# Arduino_Micro_DRAM_Tester_2.net
KiCad netlist of a schematic drawn in EAGLE
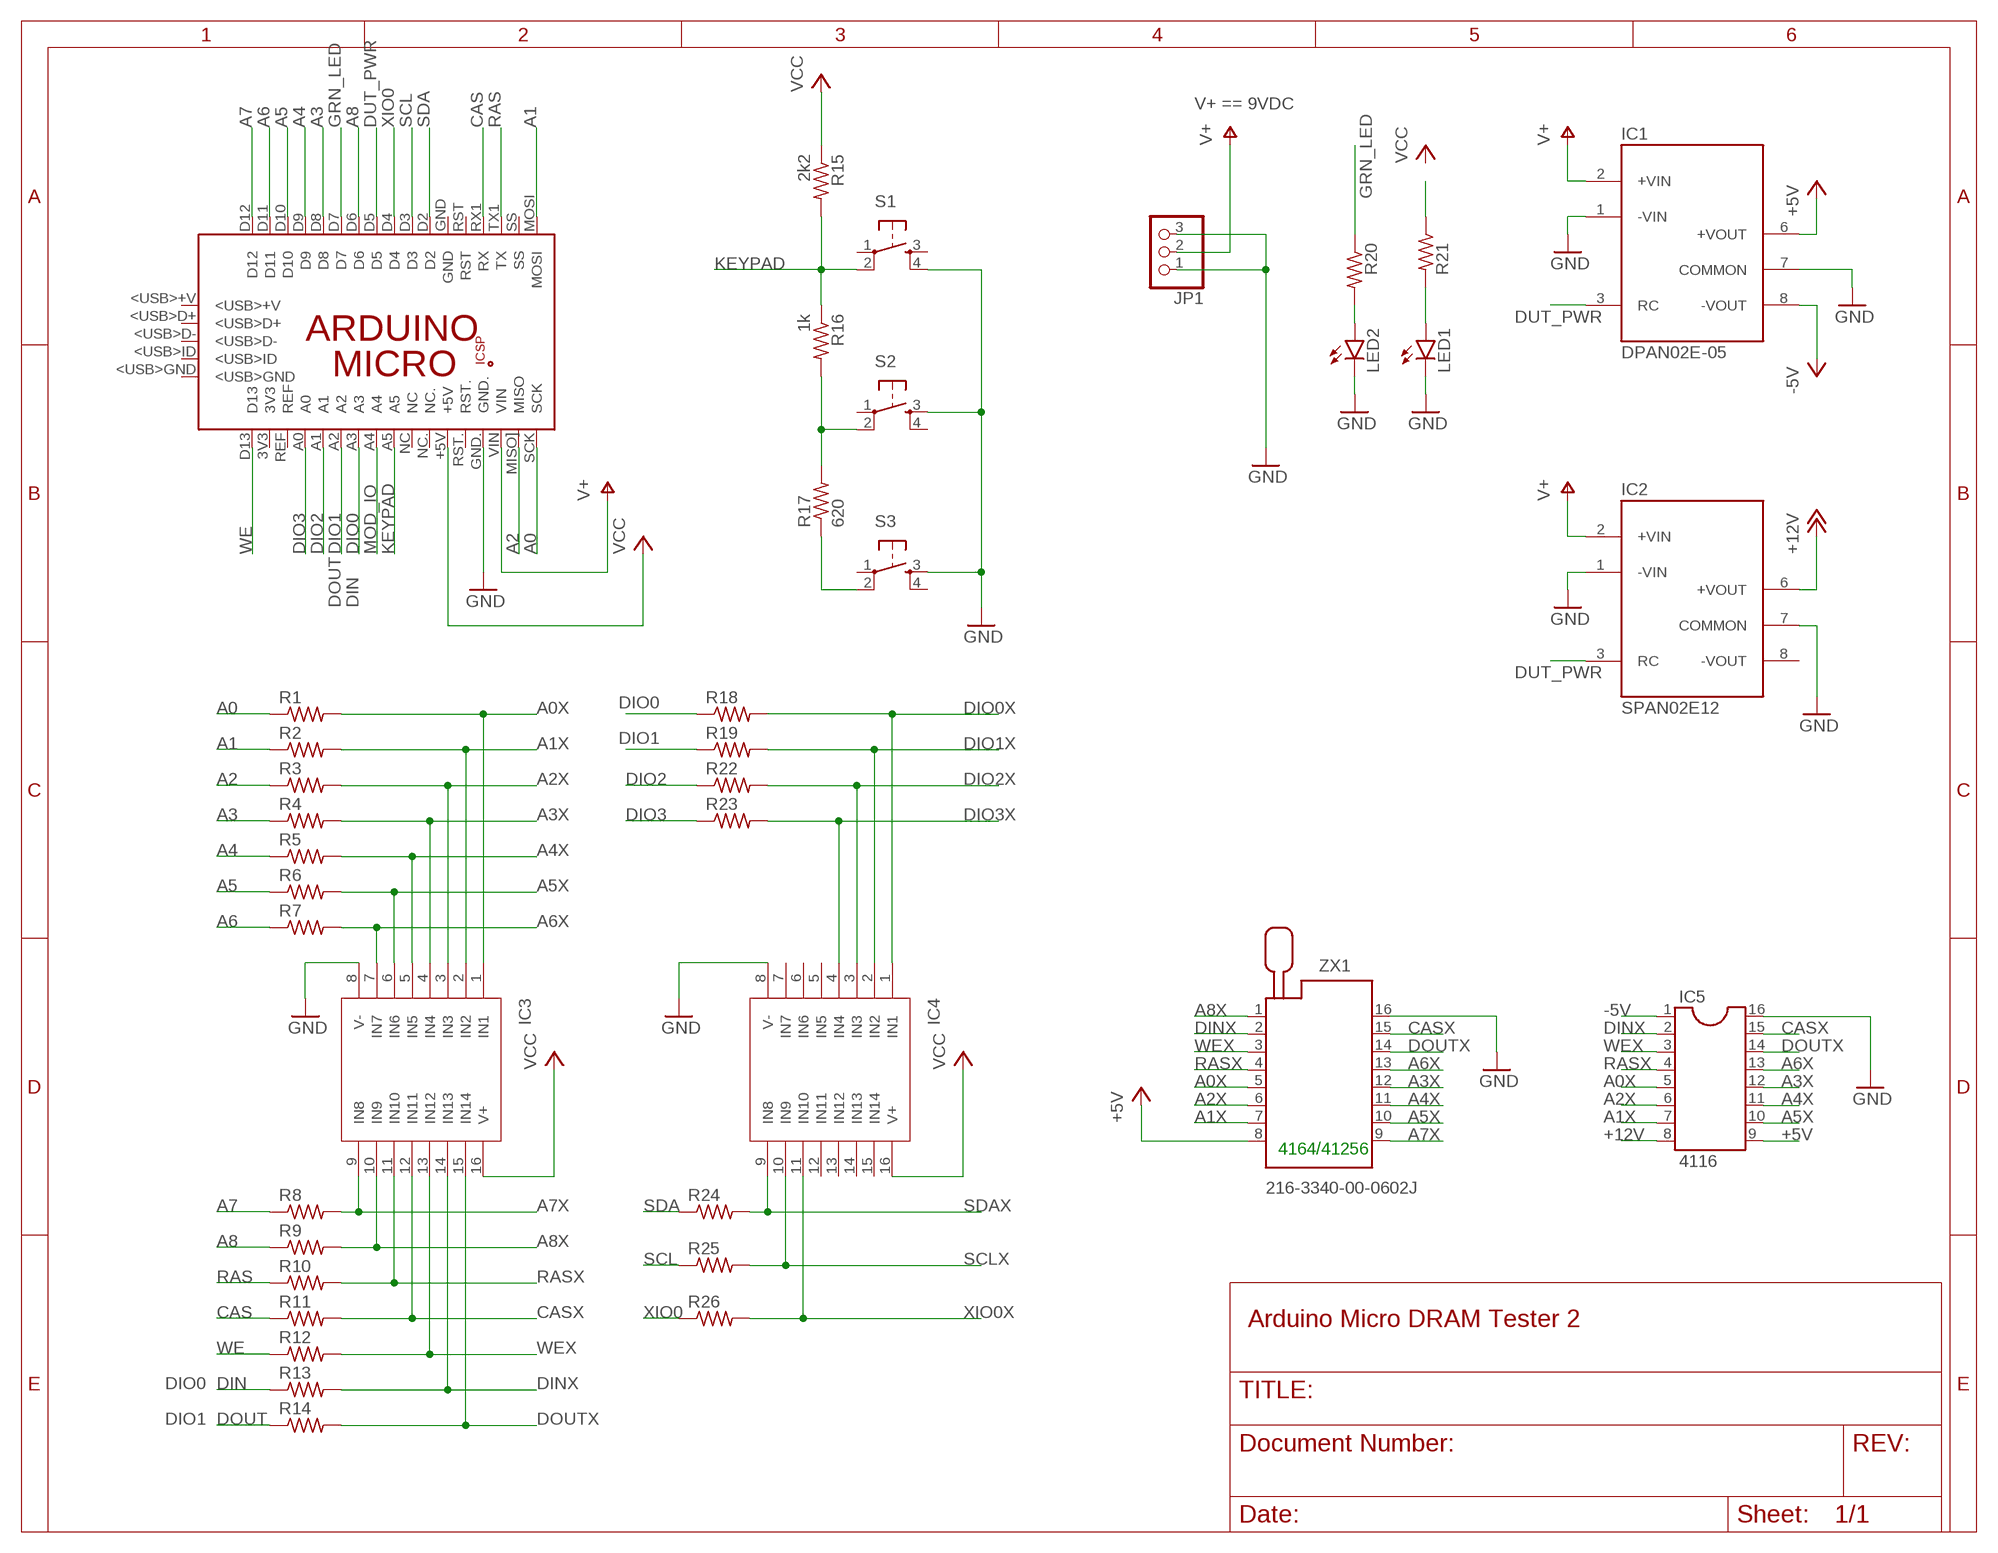
[diagram p0: schematic, sheet 1]

(export (version "E")
  (design (tool "Eeschema 10.0.6"))
  (components
    (comp (ref "IC1")
      (value "DPAN02E-05")
      (footprint "eagle-import:SIP7")
      (libsource (lib "eagle-import") (part "DPAN02"))
    )
    (comp (ref "IC2")
      (value "SPAN02E12")
      (footprint "eagle-import:SIP7")
      (libsource (lib "eagle-import") (part "DPAN02"))
    )
    (comp (ref "IC3")
      (value "SP720")
      (footprint "eagle-import:DIL16")
      (libsource (lib "eagle-import") (part "SP720"))
    )
    (comp (ref "IC4")
      (value "SP720")
      (footprint "eagle-import:DIL16")
      (libsource (lib "eagle-import") (part "SP720"))
    )
    (comp (ref "IC5")
      (value "4116")
      (footprint "eagle-import:SOCKET-16")
      (libsource (lib "eagle-import") (part "DIL16S"))
    )
    (comp (ref "JP1")
      (value "PINHD-1X3/90")
      (footprint "eagle-import:1X03_90")
      (libsource (lib "eagle-import") (part "PINHD-1X3/90"))
    )
    (comp (ref "LED1")
      (value "LED5MM")
      (footprint "eagle-import:LED5MM")
      (libsource (lib "eagle-import") (part "LED5MM"))
    )
    (comp (ref "LED2")
      (value "LED5MM")
      (footprint "eagle-import:LED5MM")
      (libsource (lib "eagle-import") (part "LED5MM"))
    )
    (comp (ref "PCB1")
      (value "ARDUINO_MICRO")
      (footprint "eagle-import:ARDUINO_MICRO")
      (libsource (lib "eagle-import") (part "ARDUINO_MICRO"))
    )
    (comp (ref "R1")
      (value "R-US_V235/17")
      (footprint "eagle-import:V235_17")
      (libsource (lib "eagle-import") (part "R-US_V235/17"))
    )
    (comp (ref "R2")
      (value "R-US_V235/17")
      (footprint "eagle-import:V235_17")
      (libsource (lib "eagle-import") (part "R-US_V235/17"))
    )
    (comp (ref "R3")
      (value "R-US_V235/17")
      (footprint "eagle-import:V235_17")
      (libsource (lib "eagle-import") (part "R-US_V235/17"))
    )
    (comp (ref "R4")
      (value "R-US_V235/17")
      (footprint "eagle-import:V235_17")
      (libsource (lib "eagle-import") (part "R-US_V235/17"))
    )
    (comp (ref "R5")
      (value "R-US_V235/17")
      (footprint "eagle-import:V235_17")
      (libsource (lib "eagle-import") (part "R-US_V235/17"))
    )
    (comp (ref "R6")
      (value "R-US_V235/17")
      (footprint "eagle-import:V235_17")
      (libsource (lib "eagle-import") (part "R-US_V235/17"))
    )
    (comp (ref "R7")
      (value "R-US_V235/17")
      (footprint "eagle-import:V235_17")
      (libsource (lib "eagle-import") (part "R-US_V235/17"))
    )
    (comp (ref "R8")
      (value "R-US_V235/17")
      (footprint "eagle-import:V235_17")
      (libsource (lib "eagle-import") (part "R-US_V235/17"))
    )
    (comp (ref "R9")
      (value "R-US_V235/17")
      (footprint "eagle-import:V235_17")
      (libsource (lib "eagle-import") (part "R-US_V235/17"))
    )
    (comp (ref "R10")
      (value "R-US_V235/17")
      (footprint "eagle-import:V235_17")
      (libsource (lib "eagle-import") (part "R-US_V235/17"))
    )
    (comp (ref "R11")
      (value "R-US_V235/17")
      (footprint "eagle-import:V235_17")
      (libsource (lib "eagle-import") (part "R-US_V235/17"))
    )
    (comp (ref "R12")
      (value "R-US_V235/17")
      (footprint "eagle-import:V235_17")
      (libsource (lib "eagle-import") (part "R-US_V235/17"))
    )
    (comp (ref "R13")
      (value "R-US_V235/17")
      (footprint "eagle-import:V235_17")
      (libsource (lib "eagle-import") (part "R-US_V235/17"))
    )
    (comp (ref "R14")
      (value "R-US_V235/17")
      (footprint "eagle-import:V235_17")
      (libsource (lib "eagle-import") (part "R-US_V235/17"))
    )
    (comp (ref "R15")
      (value "2k2")
      (footprint "eagle-import:V235_17")
      (libsource (lib "eagle-import") (part "R-US_V235/17"))
    )
    (comp (ref "R16")
      (value "1k")
      (footprint "eagle-import:V235_17")
      (libsource (lib "eagle-import") (part "R-US_V235/17"))
    )
    (comp (ref "R17")
      (value "620")
      (footprint "eagle-import:V235_17")
      (libsource (lib "eagle-import") (part "R-US_V235/17"))
    )
    (comp (ref "R18")
      (value "R-US_V235/17")
      (footprint "eagle-import:V235_17")
      (libsource (lib "eagle-import") (part "R-US_V235/17"))
    )
    (comp (ref "R19")
      (value "R-US_V235/17")
      (footprint "eagle-import:V235_17")
      (libsource (lib "eagle-import") (part "R-US_V235/17"))
    )
    (comp (ref "R20")
      (value "R-US_0309/10")
      (footprint "eagle-import:0309_10")
      (libsource (lib "eagle-import") (part "resistor_348_R-US_0309/10"))
    )
    (comp (ref "R21")
      (value "R-US_0309/10")
      (footprint "eagle-import:0309_10")
      (libsource (lib "eagle-import") (part "resistor_348_R-US_0309/10"))
    )
    (comp (ref "R22")
      (value "R-US_V235/17")
      (footprint "eagle-import:V235_17")
      (libsource (lib "eagle-import") (part "R-US_V235/17"))
    )
    (comp (ref "R23")
      (value "R-US_V235/17")
      (footprint "eagle-import:V235_17")
      (libsource (lib "eagle-import") (part "R-US_V235/17"))
    )
    (comp (ref "R24")
      (value "R-US_V235/17")
      (footprint "eagle-import:V235_17")
      (libsource (lib "eagle-import") (part "R-US_V235/17"))
    )
    (comp (ref "R25")
      (value "R-US_V235/17")
      (footprint "eagle-import:V235_17")
      (libsource (lib "eagle-import") (part "R-US_V235/17"))
    )
    (comp (ref "R26")
      (value "R-US_V235/17")
      (footprint "eagle-import:V235_17")
      (libsource (lib "eagle-import") (part "R-US_V235/17"))
    )
    (comp (ref "S1")
      (value "TAC_SWITCHPTH")
      (footprint "eagle-import:TACTILE-PTH")
      (libsource (lib "eagle-import") (part "TAC_SWITCHPTH"))
    )
    (comp (ref "S2")
      (value "TAC_SWITCHPTH")
      (footprint "eagle-import:TACTILE-PTH")
      (libsource (lib "eagle-import") (part "TAC_SWITCHPTH"))
    )
    (comp (ref "S3")
      (value "TAC_SWITCHPTH")
      (footprint "eagle-import:TACTILE-PTH")
      (libsource (lib "eagle-import") (part "TAC_SWITCHPTH"))
    )
    (comp (ref "ZX1")
      (value "216-3340-00-0602J")
      (footprint "eagle-import:216-3340-00-0602J")
      (libsource (lib "eagle-import") (part "216-3340-00-0602J"))
    )
  )
  (nets
    (net (code "1") (name "+5V") (class "Default")
      (node (ref "IC1") (pin "6") (pinfunction "+VOUT_6") (pintype "passive"))
      (node (ref "IC5") (pin "9") (pinfunction "9_9") (pintype "passive"))
      (node (ref "ZX1") (pin "8") (pinfunction "8_8") (pintype "passive"))
    )
    (net (code "2") (name "+12V") (class "Default")
      (node (ref "IC2") (pin "6") (pinfunction "+VOUT_6") (pintype "passive"))
      (node (ref "IC5") (pin "8") (pinfunction "8_8") (pintype "passive"))
    )
    (net (code "3") (name "-5V") (class "Default")
      (node (ref "IC1") (pin "8") (pinfunction "-VOUT_8") (pintype "passive"))
      (node (ref "IC5") (pin "1") (pinfunction "1_1") (pintype "passive"))
    )
    (net (code "4") (name "/A0") (class "Default")
      (node (ref "PCB1") (pin "SCK") (pinfunction "SCK_SCK") (pintype "bidirectional"))
      (node (ref "R1") (pin "1") (pinfunction "1_1") (pintype "passive"))
    )
    (net (code "5") (name "/A0X") (class "Default")
      (node (ref "IC3") (pin "1") (pinfunction "IN1_1") (pintype "input"))
      (node (ref "IC5") (pin "5") (pinfunction "5_5") (pintype "passive"))
      (node (ref "R1") (pin "2") (pinfunction "2_2") (pintype "passive"))
      (node (ref "ZX1") (pin "5") (pinfunction "5_5") (pintype "passive"))
    )
    (net (code "6") (name "/A1") (class "Default")
      (node (ref "PCB1") (pin "MOSI") (pinfunction "MOSI_MOSI") (pintype "bidirectional"))
      (node (ref "R2") (pin "1") (pinfunction "1_1") (pintype "passive"))
    )
    (net (code "7") (name "/A1X") (class "Default")
      (node (ref "IC3") (pin "2") (pinfunction "IN2_2") (pintype "input"))
      (node (ref "IC5") (pin "7") (pinfunction "7_7") (pintype "passive"))
      (node (ref "R2") (pin "2") (pinfunction "2_2") (pintype "passive"))
      (node (ref "ZX1") (pin "7") (pinfunction "7_7") (pintype "passive"))
    )
    (net (code "8") (name "/A2") (class "Default")
      (node (ref "PCB1") (pin "MISO]") (pinfunction "MISO_MISO]") (pintype "bidirectional"))
      (node (ref "R3") (pin "1") (pinfunction "1_1") (pintype "passive"))
    )
    (net (code "9") (name "/A2X") (class "Default")
      (node (ref "IC3") (pin "3") (pinfunction "IN3_3") (pintype "input"))
      (node (ref "IC5") (pin "6") (pinfunction "6_6") (pintype "passive"))
      (node (ref "R3") (pin "2") (pinfunction "2_2") (pintype "passive"))
      (node (ref "ZX1") (pin "6") (pinfunction "6_6") (pintype "passive"))
    )
    (net (code "10") (name "/A3") (class "Default")
      (node (ref "PCB1") (pin "D8") (pinfunction "D8_D8") (pintype "bidirectional"))
      (node (ref "R4") (pin "1") (pinfunction "1_1") (pintype "passive"))
    )
    (net (code "11") (name "/A3X") (class "Default")
      (node (ref "IC3") (pin "4") (pinfunction "IN4_4") (pintype "input"))
      (node (ref "IC5") (pin "12") (pinfunction "12_12") (pintype "passive"))
      (node (ref "R4") (pin "2") (pinfunction "2_2") (pintype "passive"))
      (node (ref "ZX1") (pin "12") (pinfunction "12_12") (pintype "passive"))
    )
    (net (code "12") (name "/A4") (class "Default")
      (node (ref "PCB1") (pin "D9") (pinfunction "D9_D9") (pintype "bidirectional"))
      (node (ref "R5") (pin "1") (pinfunction "1_1") (pintype "passive"))
    )
    (net (code "13") (name "/A4X") (class "Default")
      (node (ref "IC3") (pin "5") (pinfunction "IN5_5") (pintype "input"))
      (node (ref "IC5") (pin "11") (pinfunction "11_11") (pintype "passive"))
      (node (ref "R5") (pin "2") (pinfunction "2_2") (pintype "passive"))
      (node (ref "ZX1") (pin "11") (pinfunction "11_11") (pintype "passive"))
    )
    (net (code "14") (name "/A5") (class "Default")
      (node (ref "PCB1") (pin "D10") (pinfunction "D10_D10") (pintype "bidirectional"))
      (node (ref "R6") (pin "1") (pinfunction "1_1") (pintype "passive"))
    )
    (net (code "15") (name "/A5X") (class "Default")
      (node (ref "IC3") (pin "6") (pinfunction "IN6_6") (pintype "input"))
      (node (ref "IC5") (pin "10") (pinfunction "10_10") (pintype "passive"))
      (node (ref "R6") (pin "2") (pinfunction "2_2") (pintype "passive"))
      (node (ref "ZX1") (pin "10") (pinfunction "10_10") (pintype "passive"))
    )
    (net (code "16") (name "/A6") (class "Default")
      (node (ref "PCB1") (pin "D11") (pinfunction "D11_D11") (pintype "bidirectional"))
      (node (ref "R7") (pin "1") (pinfunction "1_1") (pintype "passive"))
    )
    (net (code "17") (name "/A6X") (class "Default")
      (node (ref "IC3") (pin "7") (pinfunction "IN7_7") (pintype "input"))
      (node (ref "IC5") (pin "13") (pinfunction "13_13") (pintype "passive"))
      (node (ref "R7") (pin "2") (pinfunction "2_2") (pintype "passive"))
      (node (ref "ZX1") (pin "13") (pinfunction "13_13") (pintype "passive"))
    )
    (net (code "18") (name "/A7") (class "Default")
      (node (ref "PCB1") (pin "D12") (pinfunction "D12_D12") (pintype "bidirectional"))
      (node (ref "R8") (pin "1") (pinfunction "1_1") (pintype "passive"))
    )
    (net (code "19") (name "/A7X") (class "Default")
      (node (ref "IC3") (pin "9") (pinfunction "IN8_9") (pintype "input"))
      (node (ref "R8") (pin "2") (pinfunction "2_2") (pintype "passive"))
      (node (ref "ZX1") (pin "9") (pinfunction "9_9") (pintype "passive"))
    )
    (net (code "20") (name "/A8") (class "Default")
      (node (ref "PCB1") (pin "D6") (pinfunction "D6_D6") (pintype "bidirectional"))
      (node (ref "R9") (pin "1") (pinfunction "1_1") (pintype "passive"))
    )
    (net (code "21") (name "/A8X") (class "Default")
      (node (ref "IC3") (pin "10") (pinfunction "IN9_10") (pintype "input"))
      (node (ref "R9") (pin "2") (pinfunction "2_2") (pintype "passive"))
      (node (ref "ZX1") (pin "1") (pinfunction "1_1") (pintype "passive"))
    )
    (net (code "22") (name "/CAS") (class "Default")
      (node (ref "PCB1") (pin "RX1") (pinfunction "RX_RX1") (pintype "bidirectional"))
      (node (ref "R11") (pin "1") (pinfunction "1_1") (pintype "passive"))
    )
    (net (code "23") (name "/CASX") (class "Default")
      (node (ref "IC3") (pin "12") (pinfunction "IN11_12") (pintype "input"))
      (node (ref "IC5") (pin "15") (pinfunction "15_15") (pintype "passive"))
      (node (ref "R11") (pin "2") (pinfunction "2_2") (pintype "passive"))
      (node (ref "ZX1") (pin "15") (pinfunction "15_15") (pintype "passive"))
    )
    (net (code "24") (name "/DIN") (class "Default")
      (node (ref "PCB1") (pin "A3") (pinfunction "A3_A3") (pintype "bidirectional"))
      (node (ref "R13") (pin "1") (pinfunction "1_1") (pintype "passive"))
    )
    (net (code "25") (name "/DINX") (class "Default")
      (node (ref "IC3") (pin "14") (pinfunction "IN13_14") (pintype "input"))
      (node (ref "IC5") (pin "2") (pinfunction "2_2") (pintype "passive"))
      (node (ref "R13") (pin "2") (pinfunction "2_2") (pintype "passive"))
      (node (ref "ZX1") (pin "2") (pinfunction "2_2") (pintype "passive"))
    )
    (net (code "26") (name "/DIO0X") (class "Default")
      (node (ref "IC4") (pin "1") (pinfunction "IN1_1") (pintype "input"))
      (node (ref "R18") (pin "2") (pinfunction "2_2") (pintype "passive"))
    )
    (net (code "27") (name "/DIO1X") (class "Default")
      (node (ref "IC4") (pin "2") (pinfunction "IN2_2") (pintype "input"))
      (node (ref "R19") (pin "2") (pinfunction "2_2") (pintype "passive"))
    )
    (net (code "28") (name "/DIO2") (class "Default")
      (node (ref "PCB1") (pin "A1") (pinfunction "A1_A1") (pintype "bidirectional"))
      (node (ref "R22") (pin "1") (pinfunction "1_1") (pintype "passive"))
    )
    (net (code "29") (name "/DIO2X") (class "Default")
      (node (ref "IC4") (pin "3") (pinfunction "IN3_3") (pintype "input"))
      (node (ref "R22") (pin "2") (pinfunction "2_2") (pintype "passive"))
    )
    (net (code "30") (name "/DIO3") (class "Default")
      (node (ref "PCB1") (pin "A0") (pinfunction "A0_A0") (pintype "bidirectional"))
      (node (ref "R23") (pin "1") (pinfunction "1_1") (pintype "passive"))
    )
    (net (code "31") (name "/DIO3X") (class "Default")
      (node (ref "IC4") (pin "4") (pinfunction "IN4_4") (pintype "input"))
      (node (ref "R23") (pin "2") (pinfunction "2_2") (pintype "passive"))
    )
    (net (code "32") (name "/DOUT") (class "Default")
      (node (ref "PCB1") (pin "A2") (pinfunction "A2_A2") (pintype "bidirectional"))
      (node (ref "R14") (pin "1") (pinfunction "1_1") (pintype "passive"))
    )
    (net (code "33") (name "/DOUTX") (class "Default")
      (node (ref "IC3") (pin "15") (pinfunction "IN14_15") (pintype "input"))
      (node (ref "IC5") (pin "14") (pinfunction "14_14") (pintype "passive"))
      (node (ref "R14") (pin "2") (pinfunction "2_2") (pintype "passive"))
      (node (ref "ZX1") (pin "14") (pinfunction "14_14") (pintype "passive"))
    )
    (net (code "34") (name "/DUT_PWR") (class "Default")
      (node (ref "IC1") (pin "3") (pinfunction "RC_3") (pintype "input"))
      (node (ref "IC2") (pin "3") (pinfunction "RC_3") (pintype "input"))
      (node (ref "PCB1") (pin "D5") (pinfunction "D5_D5") (pintype "bidirectional"))
    )
    (net (code "35") (name "/GRN_LED") (class "Default")
      (node (ref "PCB1") (pin "D7") (pinfunction "D7_D7") (pintype "bidirectional"))
      (node (ref "R20") (pin "1") (pinfunction "1_1") (pintype "passive"))
    )
    (net (code "36") (name "/KEYPAD") (class "Default")
      (node (ref "PCB1") (pin "A5") (pinfunction "A5_A5") (pintype "bidirectional"))
      (node (ref "R15") (pin "2") (pinfunction "2_2") (pintype "passive"))
      (node (ref "R16") (pin "1") (pinfunction "1_1") (pintype "passive"))
      (node (ref "S1") (pin "2") (pinfunction "2_2") (pintype "passive"))
    )
    (net (code "37") (name "/MOD_IO") (class "Default")
      (node (ref "PCB1") (pin "A4") (pinfunction "A4_A4") (pintype "bidirectional"))
    )
    (net (code "38") (name "/RAS") (class "Default")
      (node (ref "PCB1") (pin "TX1") (pinfunction "TX_TX1") (pintype "bidirectional"))
      (node (ref "R10") (pin "1") (pinfunction "1_1") (pintype "passive"))
    )
    (net (code "39") (name "/RASX") (class "Default")
      (node (ref "IC3") (pin "11") (pinfunction "IN10_11") (pintype "input"))
      (node (ref "IC5") (pin "4") (pinfunction "4_4") (pintype "passive"))
      (node (ref "R10") (pin "2") (pinfunction "2_2") (pintype "passive"))
      (node (ref "ZX1") (pin "4") (pinfunction "4_4") (pintype "passive"))
    )
    (net (code "40") (name "/SCL") (class "Default")
      (node (ref "PCB1") (pin "D3") (pinfunction "D3_D3") (pintype "bidirectional"))
      (node (ref "R25") (pin "1") (pinfunction "1_1") (pintype "passive"))
    )
    (net (code "41") (name "/SCLX") (class "Default")
      (node (ref "IC4") (pin "10") (pinfunction "IN9_10") (pintype "input"))
      (node (ref "R25") (pin "2") (pinfunction "2_2") (pintype "passive"))
    )
    (net (code "42") (name "/SDA") (class "Default")
      (node (ref "PCB1") (pin "D2") (pinfunction "D2_D2") (pintype "bidirectional"))
      (node (ref "R24") (pin "1") (pinfunction "1_1") (pintype "passive"))
    )
    (net (code "43") (name "/SDAX") (class "Default")
      (node (ref "IC4") (pin "9") (pinfunction "IN8_9") (pintype "input"))
      (node (ref "R24") (pin "2") (pinfunction "2_2") (pintype "passive"))
    )
    (net (code "44") (name "/WE") (class "Default")
      (node (ref "PCB1") (pin "D13") (pinfunction "D13_D13") (pintype "bidirectional"))
      (node (ref "R12") (pin "1") (pinfunction "1_1") (pintype "passive"))
    )
    (net (code "45") (name "/WEX") (class "Default")
      (node (ref "IC3") (pin "13") (pinfunction "IN12_13") (pintype "input"))
      (node (ref "IC5") (pin "3") (pinfunction "3_3") (pintype "passive"))
      (node (ref "R12") (pin "2") (pinfunction "2_2") (pintype "passive"))
      (node (ref "ZX1") (pin "3") (pinfunction "3_3") (pintype "passive"))
    )
    (net (code "46") (name "/XIO0") (class "Default")
      (node (ref "PCB1") (pin "D4") (pinfunction "D4_D4") (pintype "bidirectional"))
      (node (ref "R26") (pin "1") (pinfunction "1_1") (pintype "passive"))
    )
    (net (code "47") (name "/XIO0X") (class "Default")
      (node (ref "IC4") (pin "11") (pinfunction "IN10_11") (pintype "input"))
      (node (ref "R26") (pin "2") (pinfunction "2_2") (pintype "passive"))
    )
    (net (code "48") (name "GND") (class "Default")
      (node (ref "IC1") (pin "1") (pinfunction "-VIN_1") (pintype "input"))
      (node (ref "IC1") (pin "7") (pinfunction "COMMON_7") (pintype "passive"))
      (node (ref "IC2") (pin "1") (pinfunction "-VIN_1") (pintype "input"))
      (node (ref "IC2") (pin "7") (pinfunction "COMMON_7") (pintype "passive"))
      (node (ref "IC3") (pin "8") (pinfunction "V-_8") (pintype "input"))
      (node (ref "IC4") (pin "8") (pinfunction "V-_8") (pintype "input"))
      (node (ref "IC5") (pin "16") (pinfunction "16_16") (pintype "passive"))
      (node (ref "JP1") (pin "1") (pinfunction "1_1") (pintype "passive"))
      (node (ref "JP1") (pin "3") (pinfunction "3_3") (pintype "passive"))
      (node (ref "LED1") (pin "K") (pinfunction "C_K") (pintype "passive"))
      (node (ref "LED2") (pin "K") (pinfunction "C_K") (pintype "passive"))
      (node (ref "PCB1") (pin "GND.") (pinfunction "GND._GND.") (pintype "bidirectional"))
      (node (ref "S1") (pin "4") (pinfunction "4_4") (pintype "passive"))
      (node (ref "S2") (pin "3") (pinfunction "3_3") (pintype "passive"))
      (node (ref "S3") (pin "3") (pinfunction "3_3") (pintype "passive"))
      (node (ref "ZX1") (pin "16") (pinfunction "16_16") (pintype "passive"))
    )
    (net (code "49") (name "Net-(LED1-PadA)") (class "Default")
      (node (ref "LED1") (pin "A") (pinfunction "A_A") (pintype "passive"))
      (node (ref "R21") (pin "2") (pinfunction "2_2") (pintype "passive"))
    )
    (net (code "50") (name "Net-(LED2-PadA)") (class "Default")
      (node (ref "LED2") (pin "A") (pinfunction "A_A") (pintype "passive"))
      (node (ref "R20") (pin "2") (pinfunction "2_2") (pintype "passive"))
    )
    (net (code "51") (name "Net-(R16-Pad2)") (class "Default")
      (node (ref "R16") (pin "2") (pinfunction "2_2") (pintype "passive"))
      (node (ref "R17") (pin "2") (pinfunction "2_2") (pintype "passive"))
      (node (ref "S2") (pin "2") (pinfunction "2_2") (pintype "passive"))
    )
    (net (code "52") (name "Net-(R17-Pad1)") (class "Default")
      (node (ref "R17") (pin "1") (pinfunction "1_1") (pintype "passive"))
      (node (ref "S3") (pin "2") (pinfunction "2_2") (pintype "passive"))
    )
    (net (code "53") (name "V+") (class "Default")
      (node (ref "IC1") (pin "2") (pinfunction "+VIN_2") (pintype "input"))
      (node (ref "IC2") (pin "2") (pinfunction "+VIN_2") (pintype "input"))
      (node (ref "JP1") (pin "2") (pinfunction "2_2") (pintype "passive"))
      (node (ref "PCB1") (pin "VIN") (pinfunction "VIN_VIN") (pintype "bidirectional"))
    )
    (net (code "54") (name "VCC") (class "Default")
      (node (ref "IC3") (pin "16") (pinfunction "V+_16") (pintype "input"))
      (node (ref "IC4") (pin "16") (pinfunction "V+_16") (pintype "input"))
      (node (ref "PCB1") (pin "+5V") (pinfunction "+5V_+5V") (pintype "bidirectional"))
      (node (ref "R15") (pin "1") (pinfunction "1_1") (pintype "passive"))
    )
    (net (code "55") (name "unconnected-(IC2--VOUT-Pad8)") (class "Default")
      (node (ref "IC2") (pin "8") (pinfunction "-VOUT_8") (pintype "passive"))
    )
    (net (code "56") (name "unconnected-(IC4-IN5-Pad5)") (class "Default")
      (node (ref "IC4") (pin "5") (pinfunction "IN5_5") (pintype "input"))
    )
    (net (code "57") (name "unconnected-(IC4-IN6-Pad6)") (class "Default")
      (node (ref "IC4") (pin "6") (pinfunction "IN6_6") (pintype "input"))
    )
    (net (code "58") (name "unconnected-(IC4-IN7-Pad7)") (class "Default")
      (node (ref "IC4") (pin "7") (pinfunction "IN7_7") (pintype "input"))
    )
    (net (code "59") (name "unconnected-(IC4-IN11-Pad12)") (class "Default")
      (node (ref "IC4") (pin "12") (pinfunction "IN11_12") (pintype "input"))
    )
    (net (code "60") (name "unconnected-(IC4-IN12-Pad13)") (class "Default")
      (node (ref "IC4") (pin "13") (pinfunction "IN12_13") (pintype "input"))
    )
    (net (code "61") (name "unconnected-(IC4-IN13-Pad14)") (class "Default")
      (node (ref "IC4") (pin "14") (pinfunction "IN13_14") (pintype "input"))
    )
    (net (code "62") (name "unconnected-(IC4-IN14-Pad15)") (class "Default")
      (node (ref "IC4") (pin "15") (pinfunction "IN14_15") (pintype "input"))
    )
    (net (code "63") (name "unconnected-(PCB1-Pad3V3)") (class "Default")
      (node (ref "PCB1") (pin "3V3") (pinfunction "3V3_3V3") (pintype "bidirectional"))
    )
    (net (code "64") (name "unconnected-(PCB1-Pad5V)") (class "Default")
      (node (ref "PCB1") (pin "5V") (pinfunction "5V_5V") (pintype "bidirectional"))
    )
    (net (code "65") (name "unconnected-(PCB1-Pad<USB>+V)") (class "Default")
      (node (ref "PCB1") (pin "<USB>+V") (pinfunction "<USB>+V_<USB>+V") (pintype "bidirectional"))
    )
    (net (code "66") (name "unconnected-(PCB1-Pad<USB>D+)") (class "Default")
      (node (ref "PCB1") (pin "<USB>D+") (pinfunction "<USB>D+_<USB>D+") (pintype "bidirectional"))
    )
    (net (code "67") (name "unconnected-(PCB1-Pad<USB>D-)") (class "Default")
      (node (ref "PCB1") (pin "<USB>D-") (pinfunction "<USB>D-_<USB>D-") (pintype "bidirectional"))
    )
    (net (code "68") (name "unconnected-(PCB1-Pad<USB>GND)") (class "Default")
      (node (ref "PCB1") (pin "<USB>GND") (pinfunction "<USB>GND_<USB>GND") (pintype "bidirectional"))
    )
    (net (code "69") (name "unconnected-(PCB1-Pad<USB>ID)") (class "Default")
      (node (ref "PCB1") (pin "<USB>ID") (pinfunction "<USB>ID_<USB>ID") (pintype "bidirectional"))
    )
    (net (code "70") (name "unconnected-(PCB1-PadGND)") (class "Default")
      (node (ref "PCB1") (pin "GND") (pinfunction "GND_GND") (pintype "bidirectional"))
    )
    (net (code "71") (name "unconnected-(PCB1-PadGND_)") (class "Default")
      (node (ref "PCB1") (pin "GND_") (pinfunction "GND__GND_") (pintype "bidirectional"))
    )
    (net (code "72") (name "unconnected-(PCB1-PadMISO.)") (class "Default")
      (node (ref "PCB1") (pin "MISO.") (pinfunction "MISO._MISO.") (pintype "bidirectional"))
    )
    (net (code "73") (name "unconnected-(PCB1-PadMOSI.)") (class "Default")
      (node (ref "PCB1") (pin "MOSI.") (pinfunction "MOSI._MOSI.") (pintype "bidirectional"))
    )
    (net (code "74") (name "unconnected-(PCB1-PadNC)") (class "Default")
      (node (ref "PCB1") (pin "NC") (pinfunction "NC_NC") (pintype "bidirectional"))
    )
    (net (code "75") (name "unconnected-(PCB1-PadNC.)") (class "Default")
      (node (ref "PCB1") (pin "NC.") (pinfunction "NC._NC.") (pintype "bidirectional"))
    )
    (net (code "76") (name "unconnected-(PCB1-PadREF)") (class "Default")
      (node (ref "PCB1") (pin "REF") (pinfunction "REF_REF") (pintype "bidirectional"))
    )
    (net (code "77") (name "unconnected-(PCB1-PadRESET..)") (class "Default")
      (node (ref "PCB1") (pin "RESET..") (pinfunction "RESET.._RESET..") (pintype "bidirectional"))
    )
    (net (code "78") (name "unconnected-(PCB1-PadRST)") (class "Default")
      (node (ref "PCB1") (pin "RST") (pinfunction "RST_RST") (pintype "bidirectional"))
    )
    (net (code "79") (name "unconnected-(PCB1-PadRST.)") (class "Default")
      (node (ref "PCB1") (pin "RST.") (pinfunction "RST._RST.") (pintype "bidirectional"))
    )
    (net (code "80") (name "unconnected-(PCB1-PadSCK.)") (class "Default")
      (node (ref "PCB1") (pin "SCK.") (pinfunction "SCK._SCK.") (pintype "bidirectional"))
    )
    (net (code "81") (name "unconnected-(PCB1-PadSS)") (class "Default")
      (node (ref "PCB1") (pin "SS") (pinfunction "SS_SS") (pintype "bidirectional"))
    )
    (net (code "82") (name "unconnected-(R18-Pad1)") (class "Default")
      (node (ref "R18") (pin "1") (pinfunction "1_1") (pintype "passive"))
    )
    (net (code "83") (name "unconnected-(R19-Pad1)") (class "Default")
      (node (ref "R19") (pin "1") (pinfunction "1_1") (pintype "passive"))
    )
    (net (code "84") (name "unconnected-(R21-Pad1)") (class "Default")
      (node (ref "R21") (pin "1") (pinfunction "1_1") (pintype "passive"))
    )
    (net (code "85") (name "unconnected-(S1-Pad1)") (class "Default")
      (node (ref "S1") (pin "1") (pinfunction "1_1") (pintype "passive"))
    )
    (net (code "86") (name "unconnected-(S1-Pad3)") (class "Default")
      (node (ref "S1") (pin "3") (pinfunction "3_3") (pintype "passive"))
    )
    (net (code "87") (name "unconnected-(S2-Pad1)") (class "Default")
      (node (ref "S2") (pin "1") (pinfunction "1_1") (pintype "passive"))
    )
    (net (code "88") (name "unconnected-(S2-Pad4)") (class "Default")
      (node (ref "S2") (pin "4") (pinfunction "4_4") (pintype "passive"))
    )
    (net (code "89") (name "unconnected-(S3-Pad1)") (class "Default")
      (node (ref "S3") (pin "1") (pinfunction "1_1") (pintype "passive"))
    )
    (net (code "90") (name "unconnected-(S3-Pad4)") (class "Default")
      (node (ref "S3") (pin "4") (pinfunction "4_4") (pintype "passive"))
    )
  )
)
